# YarnControl_Connect_v1_2.net
KiCad netlist of a schematic drawn in Altium Designer
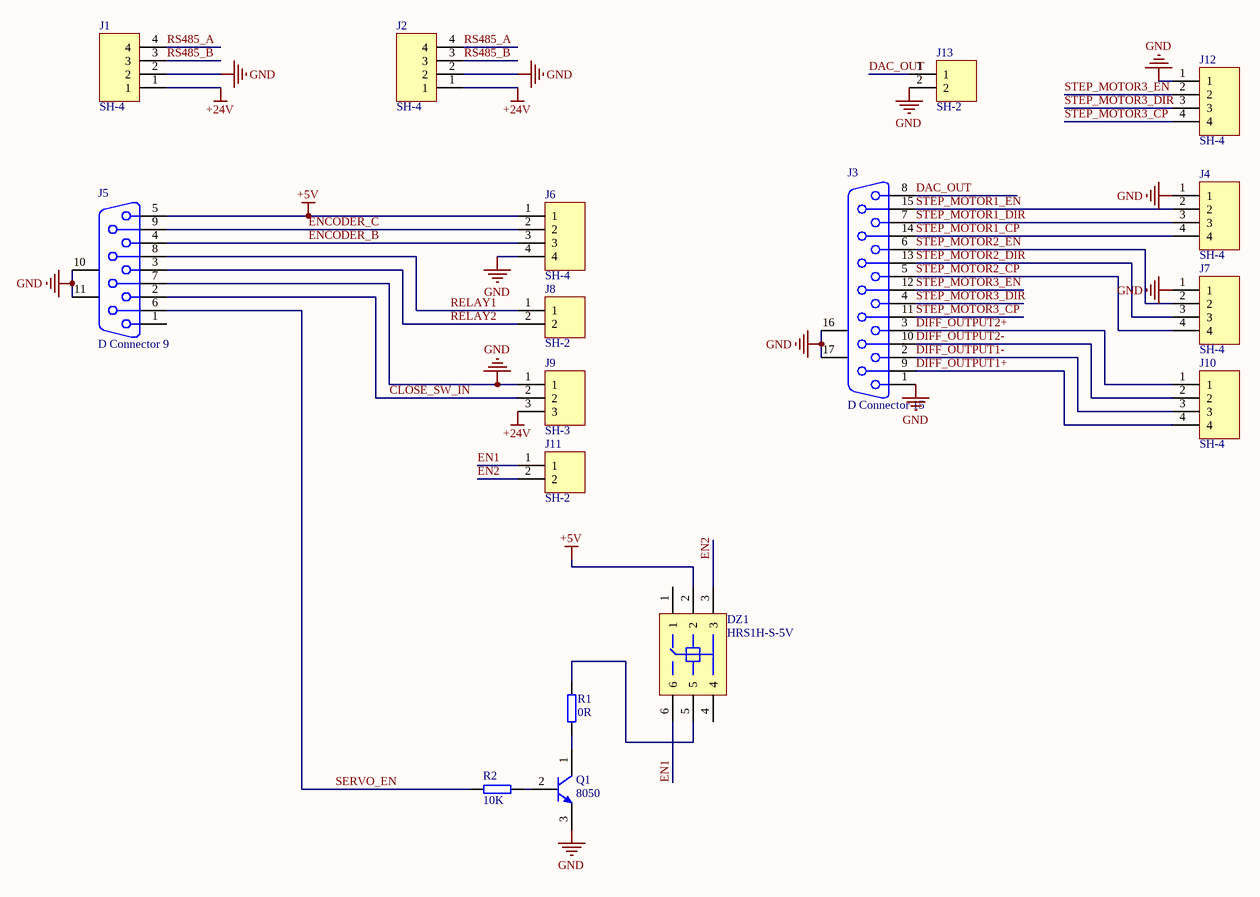
[diagram p0: YarnControl_Connect_v1.2.SchDoc]

(export (version "E")
  (design (tool "Eeschema 10.0.6"))
  (components
    (comp (ref "DZ1")
      (value "HRS1H-S-5V")
      (footprint "HRS1H-S-DC5")
      (libsource (lib "Componet") (part "HRS1H-S-5V"))
    )
    (comp (ref "J1") (value "SH-4") (footprint "PWR") (libsource (lib "") (part "SH-4_1")))
    (comp (ref "J2") (value "SH-4") (footprint "PWR") (libsource (lib "") (part "SH-4_1")))
    (comp (ref "J3")
      (value "D Connector 15")
      (footprint "DSUB1.385-2H15")
      (description "Receptacle Assembly, 15 Position, Right Angle")
      (fields (field (name "PUBLISHER") "Altium Limited"))
      (libsource (lib "Miscellaneous Connectors") (part "D Connector 15"))
    )
    (comp (ref "J4") (value "SH-4") (footprint "PWR") (libsource (lib "Connector") (part "SH-4")))
    (comp (ref "J5")
      (value "D Connector 9")
      (footprint "DSUB1.385-2H9")
      (description "Receptacle Assembly, 9 Position, Right Angle")
      (fields (field (name "PUBLISHER") "Altium Limited"))
      (libsource (lib "Miscellaneous Connectors") (part "D Connector 9"))
    )
    (comp (ref "J6") (value "SH-4") (footprint "PWR") (libsource (lib "Connector") (part "SH-4")))
    (comp (ref "J7") (value "SH-4") (footprint "PWR") (libsource (lib "Connector") (part "SH-4")))
    (comp (ref "J8") (value "SH-2") (footprint "J508-2(1)") (libsource (lib "Connector") (part "SH-2")))
    (comp (ref "J9") (value "SH-3") (footprint "J508-3") (libsource (lib "Connector") (part "SH-3")))
    (comp (ref "J10") (value "SH-4") (footprint "PWR") (libsource (lib "Connector") (part "SH-4")))
    (comp (ref "J11") (value "SH-2") (footprint "J508-2(1)") (libsource (lib "Connector") (part "SH-2")))
    (comp (ref "J12") (value "SH-4") (footprint "PWR") (libsource (lib "Connector") (part "SH-4")))
    (comp (ref "J13") (value "SH-2") (footprint "J508-2(1)") (libsource (lib "Connector") (part "SH-2")))
    (comp (ref "Q1") (value "8050") (footprint "901X") (libsource (lib "Componet") (part "NPN")))
    (comp (ref "R1")
      (value "0R")
      (footprint "RES-TH-E12")
      (description "电阻")
      (libsource (lib "Component") (part "RES"))
    )
    (comp (ref "R2")
      (value "10K")
      (footprint "RES-TH-E12")
      (description "电阻")
      (libsource (lib "Component") (part "RES"))
    )
  )
  (nets
    (net (code "1") (name "+5V") (class "Default")
      (node (ref "DZ1") (pin "2") (pinfunction "2_2") (pintype "passive"))
      (node (ref "J5") (pin "5") (pinfunction "5_5") (pintype "passive"))
      (node (ref "J6") (pin "1") (pinfunction "1_1") (pintype "passive"))
    )
    (net (code "2") (name "+24V") (class "Default")
      (node (ref "J1") (pin "1") (pinfunction "1_1") (pintype "passive"))
      (node (ref "J2") (pin "1") (pinfunction "1_1") (pintype "passive"))
      (node (ref "J9") (pin "3") (pinfunction "3_3") (pintype "passive"))
    )
    (net (code "3") (name "/CLOSE_SW_IN") (class "Default")
      (node (ref "J5") (pin "2") (pinfunction "2_2") (pintype "passive"))
      (node (ref "J9") (pin "2") (pinfunction "2_2") (pintype "passive"))
    )
    (net (code "4") (name "/DAC_OUT") (class "Default")
      (node (ref "J13") (pin "1") (pinfunction "1_1") (pintype "passive"))
      (node (ref "J3") (pin "8") (pinfunction "8_8") (pintype "passive"))
    )
    (net (code "5") (name "/DIFF_OUTPUT1+") (class "Default")
      (node (ref "J10") (pin "4") (pinfunction "4_4") (pintype "passive"))
      (node (ref "J3") (pin "9") (pinfunction "9_9") (pintype "passive"))
    )
    (net (code "6") (name "/DIFF_OUTPUT1-") (class "Default")
      (node (ref "J10") (pin "3") (pinfunction "3_3") (pintype "passive"))
      (node (ref "J3") (pin "2") (pinfunction "2_2") (pintype "passive"))
    )
    (net (code "7") (name "/DIFF_OUTPUT2+") (class "Default")
      (node (ref "J10") (pin "1") (pinfunction "1_1") (pintype "passive"))
      (node (ref "J3") (pin "3") (pinfunction "3_3") (pintype "passive"))
    )
    (net (code "8") (name "/DIFF_OUTPUT2-") (class "Default")
      (node (ref "J10") (pin "2") (pinfunction "2_2") (pintype "passive"))
      (node (ref "J3") (pin "10") (pinfunction "10_10") (pintype "passive"))
    )
    (net (code "9") (name "/EN1") (class "Default")
      (node (ref "DZ1") (pin "6") (pinfunction "6_6") (pintype "passive"))
      (node (ref "J11") (pin "1") (pinfunction "1_1") (pintype "passive"))
    )
    (net (code "10") (name "/EN2") (class "Default")
      (node (ref "DZ1") (pin "3") (pinfunction "3_3") (pintype "passive"))
      (node (ref "J11") (pin "2") (pinfunction "2_2") (pintype "passive"))
    )
    (net (code "11") (name "/ENCODER_B") (class "Default")
      (node (ref "J5") (pin "4") (pinfunction "4_4") (pintype "passive"))
      (node (ref "J6") (pin "3") (pinfunction "3_3") (pintype "passive"))
    )
    (net (code "12") (name "/ENCODER_C") (class "Default")
      (node (ref "J5") (pin "9") (pinfunction "9_9") (pintype "passive"))
      (node (ref "J6") (pin "2") (pinfunction "2_2") (pintype "passive"))
    )
    (net (code "13") (name "/RELAY1") (class "Default")
      (node (ref "J5") (pin "8") (pinfunction "8_8") (pintype "passive"))
      (node (ref "J8") (pin "1") (pinfunction "1_1") (pintype "passive"))
    )
    (net (code "14") (name "/RELAY2") (class "Default")
      (node (ref "J5") (pin "3") (pinfunction "3_3") (pintype "passive"))
      (node (ref "J8") (pin "2") (pinfunction "2_2") (pintype "passive"))
    )
    (net (code "15") (name "/RS485_A") (class "Default")
      (node (ref "J1") (pin "4") (pinfunction "4_4") (pintype "passive"))
      (node (ref "J2") (pin "4") (pinfunction "4_4") (pintype "passive"))
    )
    (net (code "16") (name "/RS485_B") (class "Default")
      (node (ref "J1") (pin "3") (pinfunction "3_3") (pintype "passive"))
      (node (ref "J2") (pin "3") (pinfunction "3_3") (pintype "passive"))
    )
    (net (code "17") (name "/SERVO_EN") (class "Default")
      (node (ref "J5") (pin "6") (pinfunction "6_6") (pintype "passive"))
      (node (ref "R2") (pin "2") (pinfunction "2_2") (pintype "passive"))
    )
    (net (code "18") (name "/STEP_MOTOR1_CP") (class "Default")
      (node (ref "J3") (pin "14") (pinfunction "14_14") (pintype "passive"))
      (node (ref "J4") (pin "4") (pinfunction "4_4") (pintype "passive"))
    )
    (net (code "19") (name "/STEP_MOTOR1_DIR") (class "Default")
      (node (ref "J3") (pin "7") (pinfunction "7_7") (pintype "passive"))
      (node (ref "J4") (pin "3") (pinfunction "3_3") (pintype "passive"))
    )
    (net (code "20") (name "/STEP_MOTOR1_EN") (class "Default")
      (node (ref "J3") (pin "15") (pinfunction "15_15") (pintype "passive"))
      (node (ref "J4") (pin "2") (pinfunction "2_2") (pintype "passive"))
    )
    (net (code "21") (name "/STEP_MOTOR2_CP") (class "Default")
      (node (ref "J3") (pin "5") (pinfunction "5_5") (pintype "passive"))
      (node (ref "J7") (pin "4") (pinfunction "4_4") (pintype "passive"))
    )
    (net (code "22") (name "/STEP_MOTOR2_DIR") (class "Default")
      (node (ref "J3") (pin "13") (pinfunction "13_13") (pintype "passive"))
      (node (ref "J7") (pin "3") (pinfunction "3_3") (pintype "passive"))
    )
    (net (code "23") (name "/STEP_MOTOR2_EN") (class "Default")
      (node (ref "J3") (pin "6") (pinfunction "6_6") (pintype "passive"))
      (node (ref "J7") (pin "2") (pinfunction "2_2") (pintype "passive"))
    )
    (net (code "24") (name "/STEP_MOTOR3_CP") (class "Default")
      (node (ref "J12") (pin "4") (pinfunction "4_4") (pintype "passive"))
      (node (ref "J3") (pin "11") (pinfunction "11_11") (pintype "passive"))
    )
    (net (code "25") (name "/STEP_MOTOR3_DIR") (class "Default")
      (node (ref "J12") (pin "3") (pinfunction "3_3") (pintype "passive"))
      (node (ref "J3") (pin "4") (pinfunction "4_4") (pintype "passive"))
    )
    (net (code "26") (name "/STEP_MOTOR3_EN") (class "Default")
      (node (ref "J12") (pin "2") (pinfunction "2_2") (pintype "passive"))
      (node (ref "J3") (pin "12") (pinfunction "12_12") (pintype "passive"))
    )
    (net (code "27") (name "GND") (class "Default")
      (node (ref "J1") (pin "2") (pinfunction "2_2") (pintype "passive"))
      (node (ref "J12") (pin "1") (pinfunction "1_1") (pintype "passive"))
      (node (ref "J13") (pin "2") (pinfunction "2_2") (pintype "passive"))
      (node (ref "J2") (pin "2") (pinfunction "2_2") (pintype "passive"))
      (node (ref "J3") (pin "1") (pinfunction "1_1") (pintype "passive"))
      (node (ref "J3") (pin "16") (pinfunction "MH1_16") (pintype "passive"))
      (node (ref "J3") (pin "17") (pinfunction "MH2_17") (pintype "passive"))
      (node (ref "J4") (pin "1") (pinfunction "1_1") (pintype "passive"))
      (node (ref "J5") (pin "10") (pinfunction "MH1_10") (pintype "passive"))
      (node (ref "J5") (pin "11") (pinfunction "MH2_11") (pintype "passive"))
      (node (ref "J5") (pin "7") (pinfunction "7_7") (pintype "passive"))
      (node (ref "J6") (pin "4") (pinfunction "4_4") (pintype "passive"))
      (node (ref "J7") (pin "1") (pinfunction "1_1") (pintype "passive"))
      (node (ref "J9") (pin "1") (pinfunction "1_1") (pintype "passive"))
      (node (ref "Q1") (pin "3") (pinfunction "E_3") (pintype "passive"))
    )
    (net (code "28") (name "Net-(DZ1-Pad5)") (class "Default")
      (node (ref "DZ1") (pin "5") (pinfunction "5_5") (pintype "passive"))
      (node (ref "R1") (pin "2") (pinfunction "2_2") (pintype "passive"))
    )
    (net (code "29") (name "Net-(Q1-B)") (class "Default")
      (node (ref "Q1") (pin "2") (pinfunction "B_2") (pintype "passive"))
      (node (ref "R2") (pin "1") (pinfunction "1_1") (pintype "passive"))
    )
    (net (code "30") (name "Net-(Q1-C)") (class "Default")
      (node (ref "Q1") (pin "1") (pinfunction "C_1") (pintype "passive"))
      (node (ref "R1") (pin "1") (pinfunction "1_1") (pintype "passive"))
    )
    (net (code "31") (name "unconnected-(DZ1-Pad1)") (class "Default")
      (node (ref "DZ1") (pin "1") (pinfunction "1_1") (pintype "passive"))
    )
    (net (code "32") (name "unconnected-(DZ1-Pad4)") (class "Default")
      (node (ref "DZ1") (pin "4") (pinfunction "4_4") (pintype "passive"))
    )
    (net (code "33") (name "unconnected-(J5-Pad1)") (class "Default")
      (node (ref "J5") (pin "1") (pinfunction "1_1") (pintype "passive"))
    )
  )
)
